# Laser_Teensy_No_AudShield_bckup.net
KiCad netlist of a schematic drawn in EAGLE
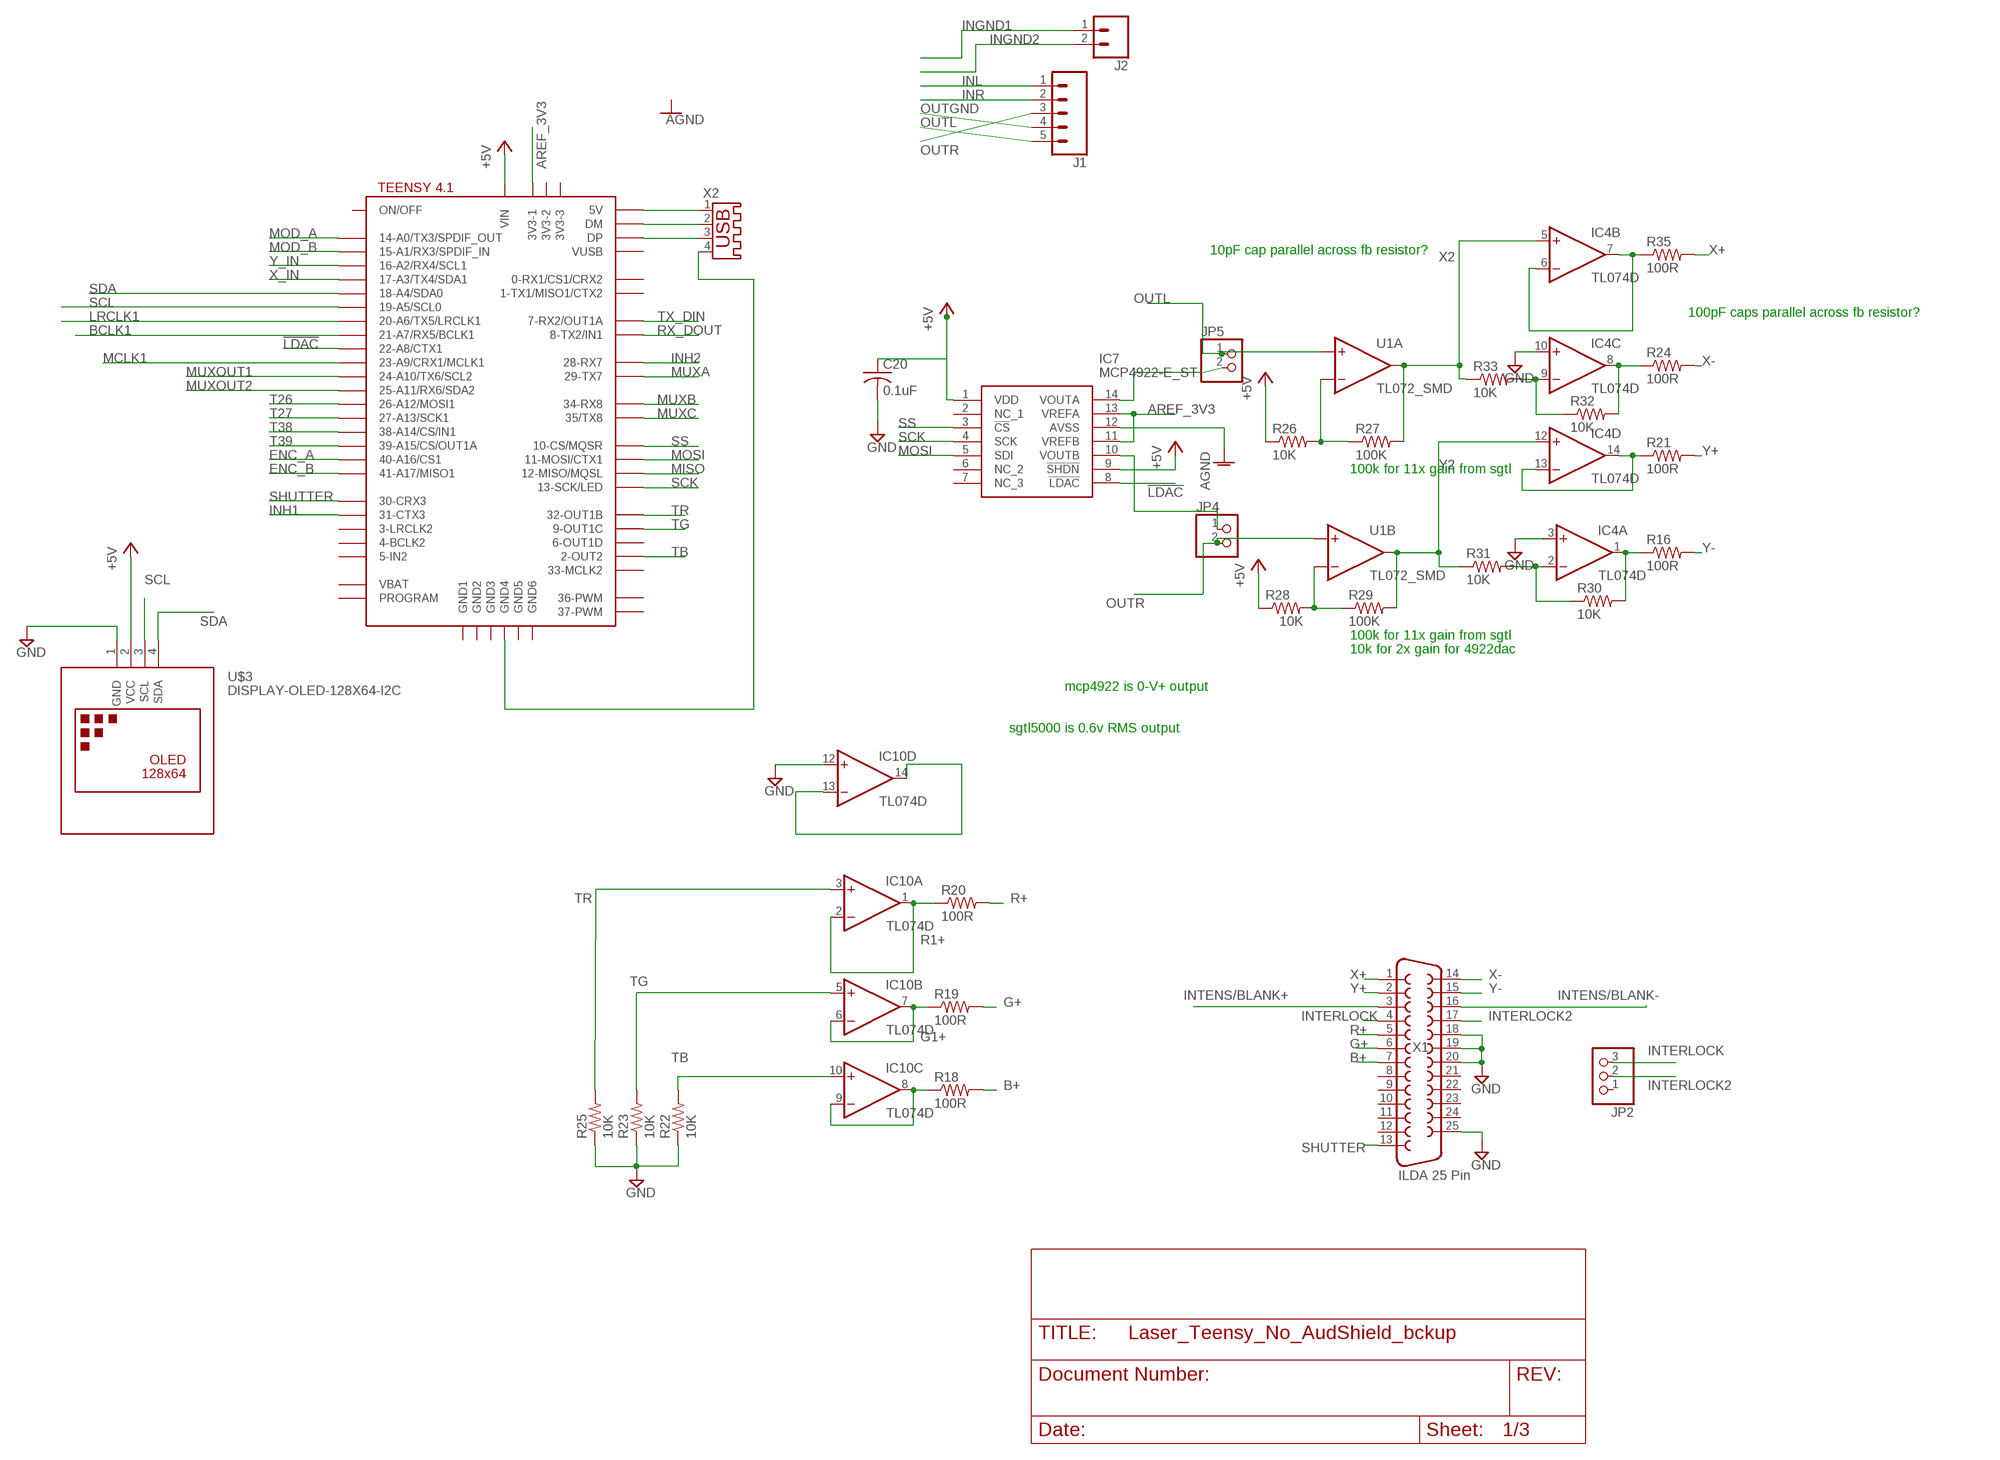
[diagram p0: schematic, sheet 1]
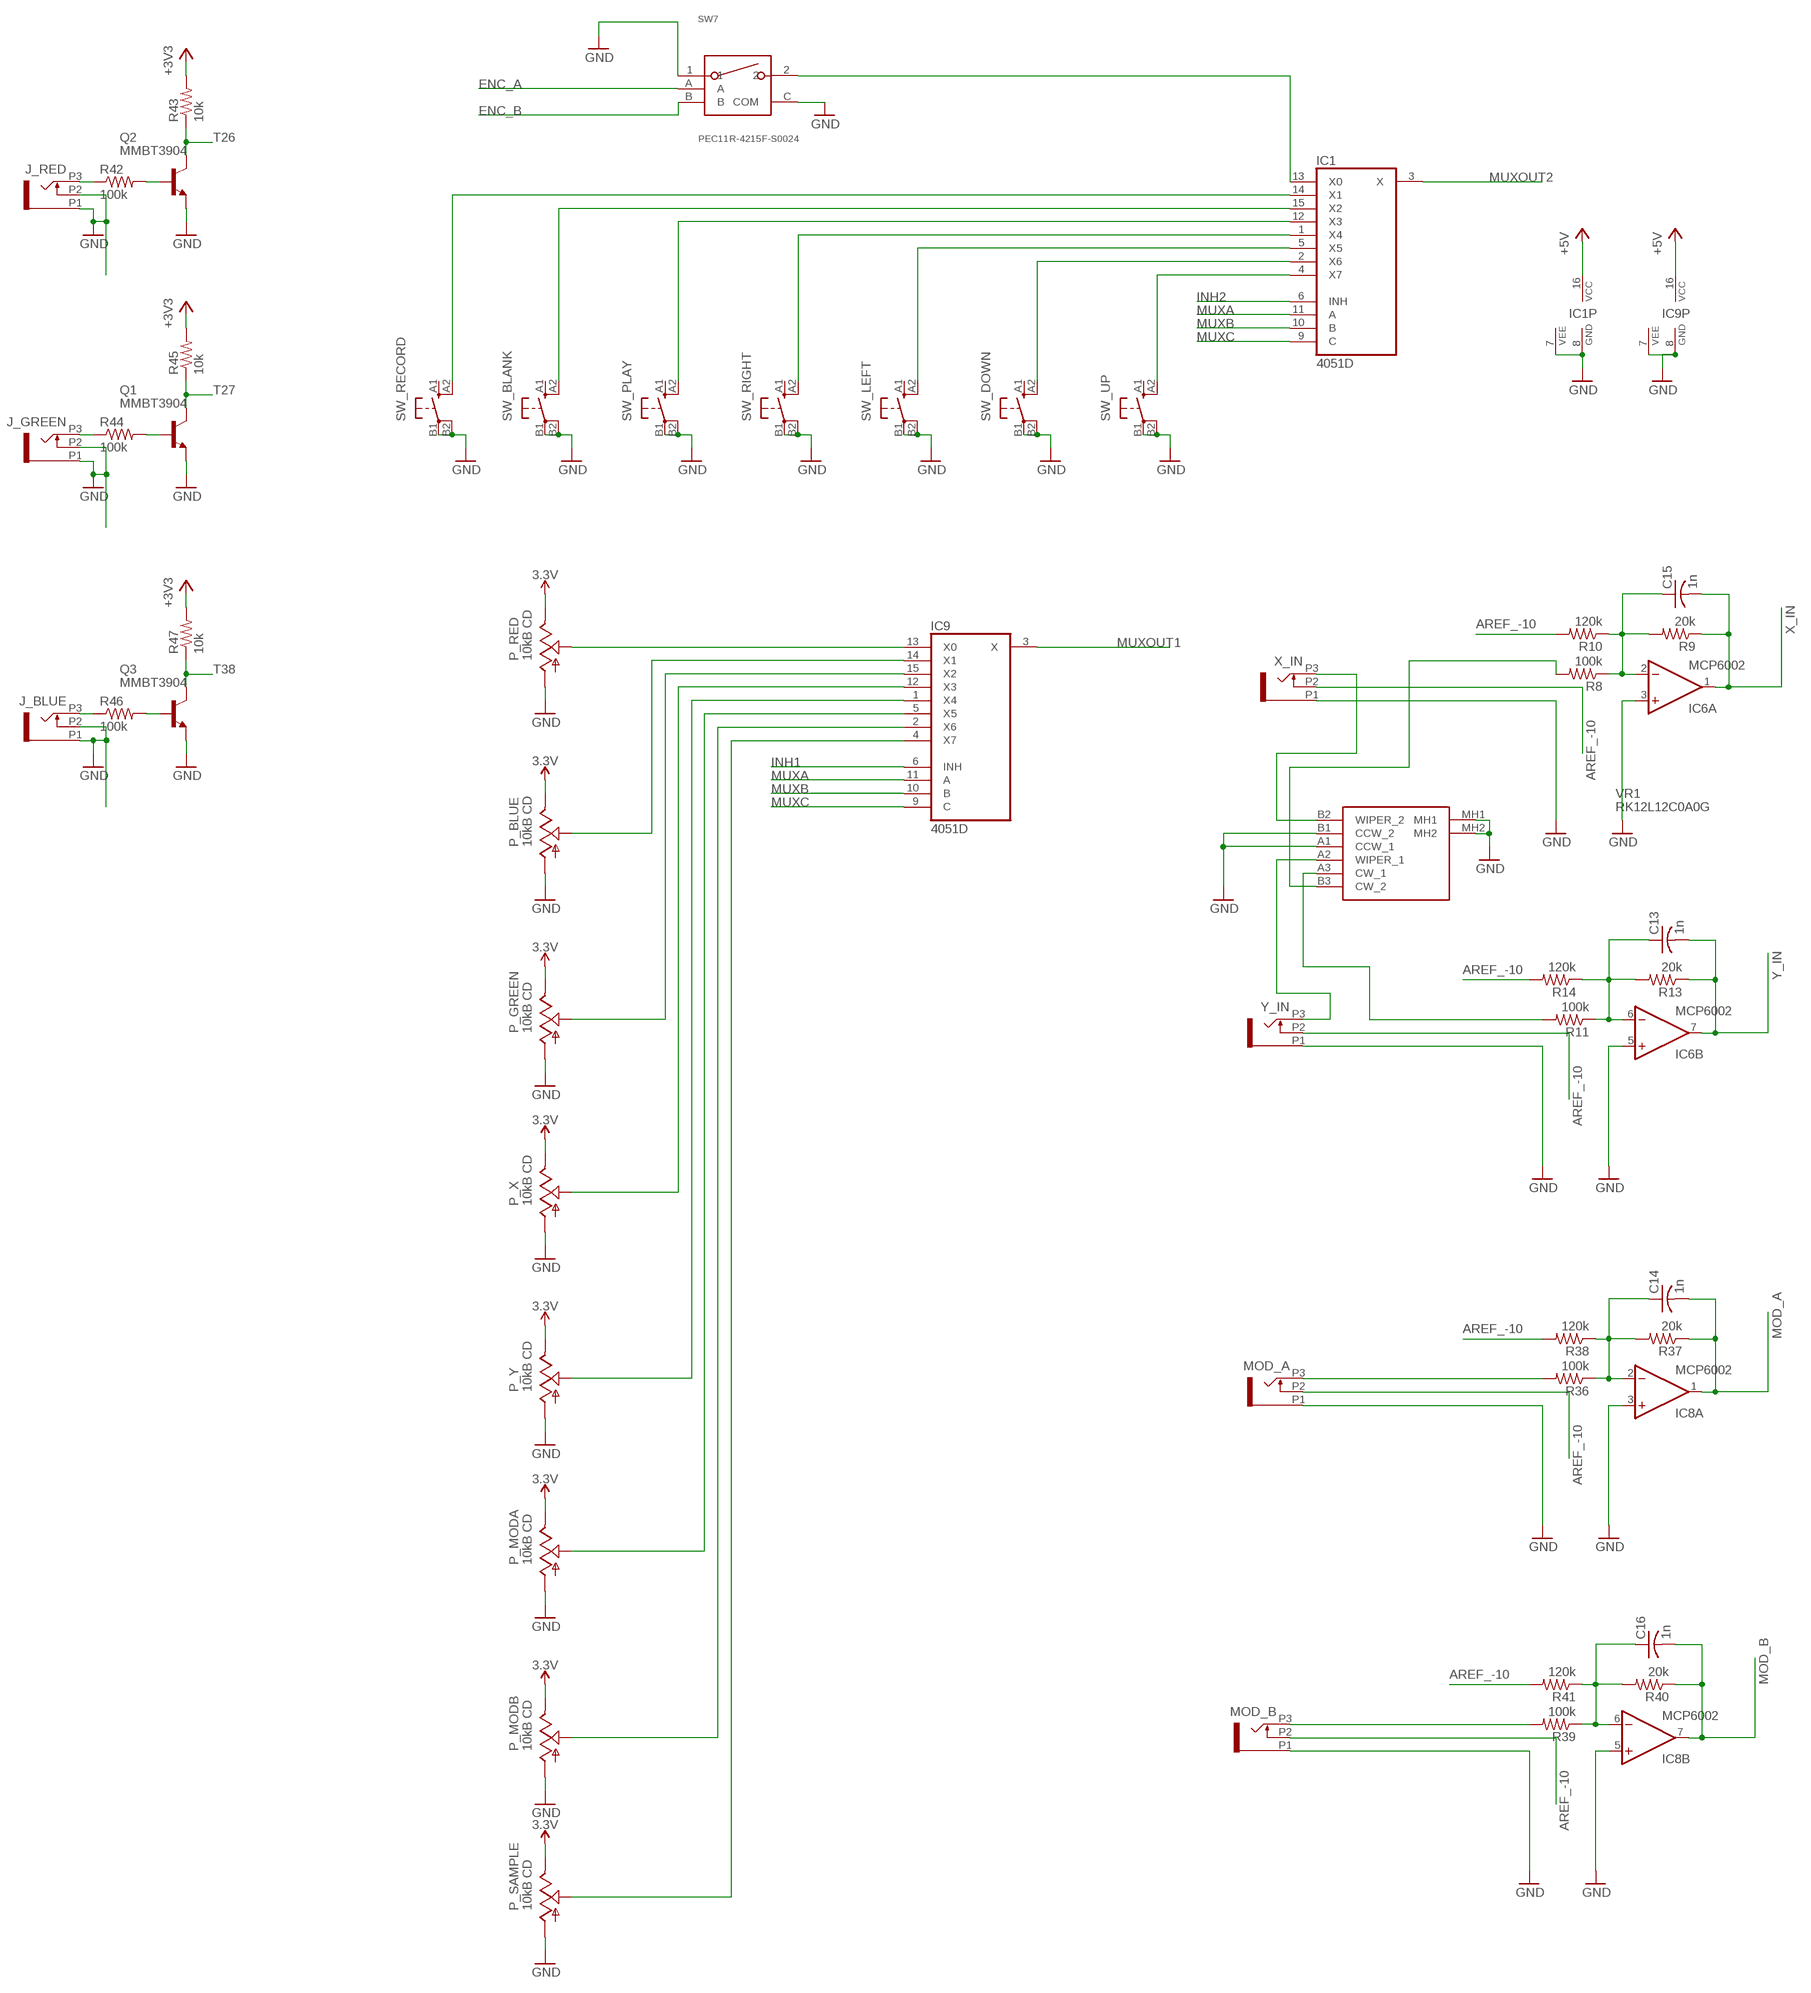
[diagram p1: schematic, sheet 2]
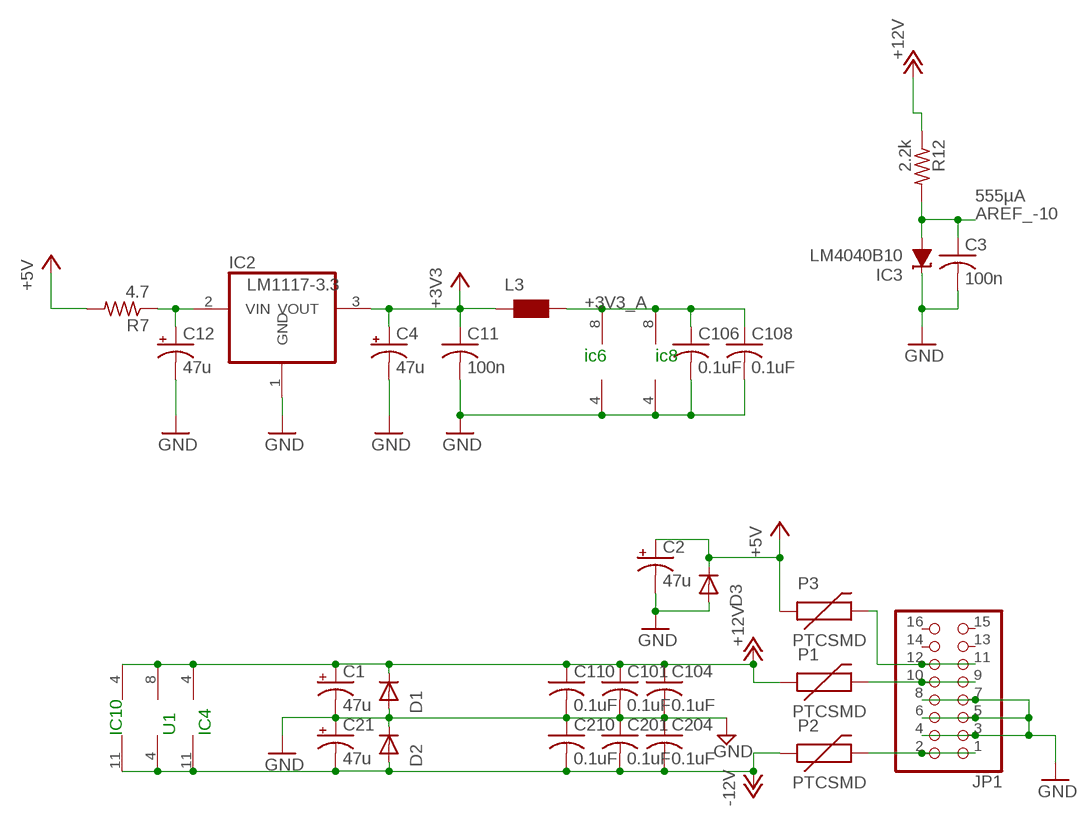
[diagram p2: schematic, sheet 3]

(export (version "E")
  (design (tool "Eeschema 10.0.6"))
  (components
    (comp (ref "C13")
      (value "1n")
      (footprint "eagle-import:C050-025X075")
      (libsource (lib "eagle-import") (part "rcl_334_C-US050-025X075"))
    )
    (comp (ref "C14")
      (value "1n")
      (footprint "eagle-import:C050-025X075")
      (libsource (lib "eagle-import") (part "rcl_334_C-US050-025X075"))
    )
    (comp (ref "C15")
      (value "1n")
      (footprint "eagle-import:C050-025X075")
      (libsource (lib "eagle-import") (part "rcl_334_C-US050-025X075"))
    )
    (comp (ref "C16")
      (value "1n")
      (footprint "eagle-import:C050-025X075")
      (libsource (lib "eagle-import") (part "rcl_334_C-US050-025X075"))
    )
    (comp (ref "IC1")
      (value "4051D")
      (footprint "eagle-import:SO16")
      (libsource (lib "eagle-import") (part "4051D"))
    )
    (comp (ref "IC6")
      (value "MCP6002")
      (footprint "eagle-import:SO08")
      (libsource (lib "eagle-import") (part "TL072D"))
    )
    (comp (ref "IC8")
      (value "MCP6002")
      (footprint "eagle-import:SO08")
      (libsource (lib "eagle-import") (part "TL072D"))
    )
    (comp (ref "IC9")
      (value "4051D")
      (footprint "eagle-import:SO16")
      (libsource (lib "eagle-import") (part "4051D"))
    )
    (comp (ref "J_BLUE")
      (value "PJ301_THONKICONN6")
      (footprint "eagle-import:WQP_PJ_301M6")
      (libsource (lib "eagle-import") (part "PJ301_THONKICONN6"))
    )
    (comp (ref "J_GREEN")
      (value "PJ301_THONKICONN6")
      (footprint "eagle-import:WQP_PJ_301M6")
      (libsource (lib "eagle-import") (part "PJ301_THONKICONN6"))
    )
    (comp (ref "J_RED")
      (value "PJ301_THONKICONN6")
      (footprint "eagle-import:WQP_PJ_301M6")
      (libsource (lib "eagle-import") (part "PJ301_THONKICONN6"))
    )
    (comp (ref "MOD_A")
      (value "PJ301_THONKICONN6")
      (footprint "eagle-import:WQP_PJ_301M6")
      (libsource (lib "eagle-import") (part "og-pj301_variations_PJ301_THONKICONN6"))
    )
    (comp (ref "MOD_B")
      (value "PJ301_THONKICONN6")
      (footprint "eagle-import:WQP_PJ_301M6")
      (libsource (lib "eagle-import") (part "og-pj301_variations_PJ301_THONKICONN6"))
    )
    (comp (ref "P_BLUE")
      (value "10kB CD")
      (footprint "eagle-import:ALPS_POT_VERTICAL_PS")
      (libsource (lib "eagle-import") (part "POT_USVERTICAL_PS"))
    )
    (comp (ref "P_GREEN")
      (value "10kB CD")
      (footprint "eagle-import:ALPS_POT_VERTICAL_PS")
      (libsource (lib "eagle-import") (part "POT_USVERTICAL_PS"))
    )
    (comp (ref "P_MODA")
      (value "10kB CD")
      (footprint "eagle-import:ALPS_POT_VERTICAL_PS")
      (libsource (lib "eagle-import") (part "POT_USVERTICAL_PS"))
    )
    (comp (ref "P_MODB")
      (value "10kB CD")
      (footprint "eagle-import:ALPS_POT_VERTICAL_PS")
      (libsource (lib "eagle-import") (part "POT_USVERTICAL_PS"))
    )
    (comp (ref "P_RED")
      (value "10kB CD")
      (footprint "eagle-import:ALPS_POT_VERTICAL_PS")
      (libsource (lib "eagle-import") (part "POT_USVERTICAL_PS"))
    )
    (comp (ref "P_SAMPLE")
      (value "10kB CD")
      (footprint "eagle-import:ALPS_POT_VERTICAL_PS")
      (libsource (lib "eagle-import") (part "POT_USVERTICAL_PS"))
    )
    (comp (ref "P_X")
      (value "10kB CD")
      (footprint "eagle-import:ALPS_POT_VERTICAL_PS")
      (libsource (lib "eagle-import") (part "POT_USVERTICAL_PS"))
    )
    (comp (ref "P_Y")
      (value "10kB CD")
      (footprint "eagle-import:ALPS_POT_VERTICAL_PS")
      (libsource (lib "eagle-import") (part "POT_USVERTICAL_PS"))
    )
    (comp (ref "Q1")
      (value "MMBT3904")
      (footprint "eagle-import:SOT23-BEC")
      (libsource (lib "eagle-import") (part "-NPN-SOT23-BECMMBT3904LT1"))
    )
    (comp (ref "Q2")
      (value "MMBT3904")
      (footprint "eagle-import:SOT23-BEC")
      (libsource (lib "eagle-import") (part "-NPN-SOT23-BECMMBT3904LT1"))
    )
    (comp (ref "Q3")
      (value "MMBT3904")
      (footprint "eagle-import:SOT23-BEC")
      (libsource (lib "eagle-import") (part "-NPN-SOT23-BECMMBT3904LT1"))
    )
    (comp (ref "R8")
      (value "100k")
      (footprint "eagle-import:0204_5")
      (libsource (lib "eagle-import") (part "rcl_334_R-US_0204/5"))
    )
    (comp (ref "R9")
      (value "20k")
      (footprint "eagle-import:0204_5")
      (libsource (lib "eagle-import") (part "rcl_334_R-US_0204/5"))
    )
    (comp (ref "R10")
      (value "120k")
      (footprint "eagle-import:0204_5")
      (libsource (lib "eagle-import") (part "rcl_334_R-US_0204/5"))
    )
    (comp (ref "R11")
      (value "100k")
      (footprint "eagle-import:0204_5")
      (libsource (lib "eagle-import") (part "rcl_334_R-US_0204/5"))
    )
    (comp (ref "R13")
      (value "20k")
      (footprint "eagle-import:0204_5")
      (libsource (lib "eagle-import") (part "rcl_334_R-US_0204/5"))
    )
    (comp (ref "R14")
      (value "120k")
      (footprint "eagle-import:0204_5")
      (libsource (lib "eagle-import") (part "rcl_334_R-US_0204/5"))
    )
    (comp (ref "R36")
      (value "100k")
      (footprint "eagle-import:0204_5")
      (libsource (lib "eagle-import") (part "rcl_334_R-US_0204/5"))
    )
    (comp (ref "R37")
      (value "20k")
      (footprint "eagle-import:0204_5")
      (libsource (lib "eagle-import") (part "rcl_334_R-US_0204/5"))
    )
    (comp (ref "R38")
      (value "120k")
      (footprint "eagle-import:0204_5")
      (libsource (lib "eagle-import") (part "rcl_334_R-US_0204/5"))
    )
    (comp (ref "R39")
      (value "100k")
      (footprint "eagle-import:0204_5")
      (libsource (lib "eagle-import") (part "rcl_334_R-US_0204/5"))
    )
    (comp (ref "R40")
      (value "20k")
      (footprint "eagle-import:0204_5")
      (libsource (lib "eagle-import") (part "rcl_334_R-US_0204/5"))
    )
    (comp (ref "R41")
      (value "120k")
      (footprint "eagle-import:0204_5")
      (libsource (lib "eagle-import") (part "rcl_334_R-US_0204/5"))
    )
    (comp (ref "R42")
      (value "100k")
      (footprint "eagle-import:0204_5")
      (libsource (lib "eagle-import") (part "rcl_334_R-US_0204/5"))
    )
    (comp (ref "R43")
      (value "10k")
      (footprint "eagle-import:0204_5")
      (libsource (lib "eagle-import") (part "rcl_334_R-US_0204/5"))
    )
    (comp (ref "R44")
      (value "100k")
      (footprint "eagle-import:0204_5")
      (libsource (lib "eagle-import") (part "rcl_334_R-US_0204/5"))
    )
    (comp (ref "R45")
      (value "10k")
      (footprint "eagle-import:0204_5")
      (libsource (lib "eagle-import") (part "rcl_334_R-US_0204/5"))
    )
    (comp (ref "R46")
      (value "100k")
      (footprint "eagle-import:0204_5")
      (libsource (lib "eagle-import") (part "rcl_334_R-US_0204/5"))
    )
    (comp (ref "R47")
      (value "10k")
      (footprint "eagle-import:0204_5")
      (libsource (lib "eagle-import") (part "rcl_334_R-US_0204/5"))
    )
    (comp (ref "SW7")
      (value "PEC11R-4215F-S0024")
      (footprint "eagle-import:PEC11R-4215F-S0024")
      (fields
        (field (name "DIGIKEY_PART_NUMBER") "PEC11R-4215F-S0024-ND")
        (field (name "MANUFACTURER") "Bourns Inc.")
        (field (name "CREATED_BY") "PCBLayout.com")
      )
      (libsource (lib "eagle-import") (part "PEC11R-4215F-S0024"))
    )
    (comp (ref "SW_BLANK")
      (value "D6R")
      (footprint "eagle-import:D6R")
      (libsource (lib "eagle-import") (part "D6R"))
    )
    (comp (ref "SW_DOWN")
      (value "D6R")
      (footprint "eagle-import:D6R")
      (libsource (lib "eagle-import") (part "D6R"))
    )
    (comp (ref "SW_LEFT")
      (value "D6R")
      (footprint "eagle-import:D6R")
      (libsource (lib "eagle-import") (part "D6R"))
    )
    (comp (ref "SW_PLAY")
      (value "D6R")
      (footprint "eagle-import:D6R")
      (libsource (lib "eagle-import") (part "D6R"))
    )
    (comp (ref "SW_RECORD")
      (value "D6R")
      (footprint "eagle-import:D6R")
      (libsource (lib "eagle-import") (part "D6R"))
    )
    (comp (ref "SW_RIGHT")
      (value "D6R")
      (footprint "eagle-import:D6R")
      (libsource (lib "eagle-import") (part "D6R"))
    )
    (comp (ref "SW_UP")
      (value "D6R")
      (footprint "eagle-import:D6R")
      (libsource (lib "eagle-import") (part "D6R"))
    )
    (comp (ref "VR1")
      (value "RK12L12C0A0G")
      (footprint "eagle-import:RK12L12C0A0G")
      (fields (field (name "MOUSER_PART_NUMBER") "688-RK12L12C0A0G"))
      (libsource (lib "eagle-import") (part "RK12L12C0A0G"))
    )
    (comp (ref "X_IN")
      (value "PJ301_THONKICONN6")
      (footprint "eagle-import:WQP_PJ_301M6")
      (libsource (lib "eagle-import") (part "og-pj301_variations_PJ301_THONKICONN6"))
    )
    (comp (ref "Y_IN")
      (value "PJ301_THONKICONN6")
      (footprint "eagle-import:WQP_PJ_301M6")
      (libsource (lib "eagle-import") (part "og-pj301_variations_PJ301_THONKICONN6"))
    )
    (comp (ref "C1")
      (value "47u")
      (footprint "eagle-import:E3,5-8")
      (libsource (lib "eagle-import") (part "CPOL-USE3.5-8"))
    )
    (comp (ref "C2")
      (value "47u")
      (footprint "eagle-import:E3,5-8")
      (libsource (lib "eagle-import") (part "CPOL-USE3.5-8"))
    )
    (comp (ref "C3")
      (value "100n")
      (footprint "eagle-import:C0603")
      (libsource (lib "eagle-import") (part "rcl_C-USC0603"))
    )
    (comp (ref "C4")
      (value "47u")
      (footprint "eagle-import:E3,5-8")
      (libsource (lib "eagle-import") (part "CPOL-USE3.5-8"))
    )
    (comp (ref "C11")
      (value "100n")
      (footprint "eagle-import:C0603")
      (libsource (lib "eagle-import") (part "rcl_C-USC0603"))
    )
    (comp (ref "C12")
      (value "47u")
      (footprint "eagle-import:E3,5-8")
      (libsource (lib "eagle-import") (part "CPOL-USE3.5-8"))
    )
    (comp (ref "C21")
      (value "47u")
      (footprint "eagle-import:E3,5-8")
      (libsource (lib "eagle-import") (part "CPOL-USE3.5-8"))
    )
    (comp (ref "C101")
      (value "0.1uF")
      (footprint "eagle-import:C0603")
      (libsource (lib "eagle-import") (part "C-USC0603"))
    )
    (comp (ref "C104")
      (value "0.1uF")
      (footprint "eagle-import:C0603")
      (libsource (lib "eagle-import") (part "C-USC0603"))
    )
    (comp (ref "C106")
      (value "0.1uF")
      (footprint "eagle-import:C0603")
      (libsource (lib "eagle-import") (part "C-USC0603"))
    )
    (comp (ref "C108")
      (value "0.1uF")
      (footprint "eagle-import:C0603")
      (libsource (lib "eagle-import") (part "C-USC0603"))
    )
    (comp (ref "C110")
      (value "0.1uF")
      (footprint "eagle-import:C0603")
      (libsource (lib "eagle-import") (part "C-USC0603"))
    )
    (comp (ref "C201")
      (value "0.1uF")
      (footprint "eagle-import:C0603")
      (libsource (lib "eagle-import") (part "C-USC0603"))
    )
    (comp (ref "C204")
      (value "0.1uF")
      (footprint "eagle-import:C0603")
      (libsource (lib "eagle-import") (part "C-USC0603"))
    )
    (comp (ref "C210")
      (value "0.1uF")
      (footprint "eagle-import:C0603")
      (libsource (lib "eagle-import") (part "C-USC0603"))
    )
    (comp (ref "D1")
      (value "1N5819HW")
      (footprint "eagle-import:SOD123")
      (libsource (lib "eagle-import") (part "DIODE-SOD123"))
    )
    (comp (ref "D2")
      (value "1N5819HW")
      (footprint "eagle-import:SOD123")
      (libsource (lib "eagle-import") (part "DIODE-SOD123"))
    )
    (comp (ref "D3")
      (value "1N5819HW")
      (footprint "eagle-import:SOD123")
      (libsource (lib "eagle-import") (part "DIODE-SOD123"))
    )
    (comp (ref "IC2")
      (value "LM1117-3.3")
      (footprint "eagle-import:TO252")
      (libsource (lib "eagle-import") (part "REG1117T"))
    )
    (comp (ref "IC3")
      (value "LM4040B10")
      (footprint "eagle-import:DBZ_R-PDSO-G3")
      (libsource (lib "eagle-import") (part "LM4041DBZB12"))
    )
    (comp (ref "IC4")
      (value "TL074D")
      (footprint "eagle-import:SO14")
      (libsource (lib "eagle-import") (part "TL074D"))
    )
    (comp (ref "IC10")
      (value "TL074D")
      (footprint "eagle-import:SO14")
      (libsource (lib "eagle-import") (part "TL074D"))
    )
    (comp (ref "JP1")
      (value "PINHD-2X8")
      (footprint "eagle-import:2X08")
      (libsource (lib "eagle-import") (part "PINHD-2X8"))
    )
    (comp (ref "L3")
      (value "WE-CBF_0603")
      (footprint "eagle-import:0603")
      (libsource (lib "eagle-import") (part "WE-CBF_0603"))
    )
    (comp (ref "P1")
      (value "PTCSMD")
      (footprint "eagle-import:PTC-1206")
      (libsource (lib "eagle-import") (part "PTCSMD"))
    )
    (comp (ref "P2")
      (value "PTCSMD")
      (footprint "eagle-import:PTC-1206")
      (libsource (lib "eagle-import") (part "PTCSMD"))
    )
    (comp (ref "P3")
      (value "PTCSMD")
      (footprint "eagle-import:PTC-1206")
      (libsource (lib "eagle-import") (part "PTCSMD"))
    )
    (comp (ref "R7")
      (value "4.7")
      (footprint "eagle-import:R1206")
      (libsource (lib "eagle-import") (part "R-US_R1206"))
    )
    (comp (ref "R12")
      (value "2.2k")
      (footprint "eagle-import:0204_5")
      (libsource (lib "eagle-import") (part "rcl_334_R-US_0204/5"))
    )
    (comp (ref "U1")
      (value "TL072_SMD")
      (footprint "eagle-import:SO08")
      (libsource (lib "eagle-import") (part "TL072_SMD"))
    )
    (comp (ref "C20")
      (value "0.1uF")
      (footprint "eagle-import:C0603")
      (libsource (lib "eagle-import") (part "C-USC0603"))
    )
    (comp (ref "IC7")
      (value "MCP4922-E_ST")
      (footprint "eagle-import:SOP65P638X110-14N")
      (fields
        (field (name "ARROW_PART_NUMBER") "MCP4922-E/ST")
        (field (name "MOUSER_PART_NUMBER") "579-MCP4922-E/ST")
      )
      (libsource (lib "eagle-import") (part "MCP4922-E_ST"))
    )
    (comp (ref "J1")
      (value "CONN_05")
      (footprint "eagle-import:1X05")
      (libsource (lib "eagle-import") (part "CONN_05"))
    )
    (comp (ref "J2")
      (value "CONN_02")
      (footprint "eagle-import:1X02")
      (libsource (lib "eagle-import") (part "CONN_02"))
    )
    (comp (ref "JP2")
      (value "PINHD-1X3")
      (footprint "eagle-import:1X03")
      (libsource (lib "eagle-import") (part "PINHD-1X3"))
    )
    (comp (ref "JP4")
      (value "PINHD-1X2")
      (footprint "eagle-import:1X02")
      (libsource (lib "eagle-import") (part "PINHD-1X2"))
    )
    (comp (ref "JP5")
      (value "PINHD-1X2")
      (footprint "eagle-import:1X02")
      (libsource (lib "eagle-import") (part "PINHD-1X2"))
    )
    (comp (ref "R16")
      (value "100R")
      (footprint "eagle-import:0204_5")
      (libsource (lib "eagle-import") (part "rcl_334_R-US_0204/5"))
    )
    (comp (ref "R18")
      (value "100R")
      (footprint "eagle-import:0204_5")
      (libsource (lib "eagle-import") (part "rcl_334_R-US_0204/5"))
    )
    (comp (ref "R19")
      (value "100R")
      (footprint "eagle-import:0204_5")
      (libsource (lib "eagle-import") (part "rcl_334_R-US_0204/5"))
    )
    (comp (ref "R20")
      (value "100R")
      (footprint "eagle-import:0204_5")
      (libsource (lib "eagle-import") (part "rcl_334_R-US_0204/5"))
    )
    (comp (ref "R21")
      (value "100R")
      (footprint "eagle-import:0204_5")
      (libsource (lib "eagle-import") (part "rcl_334_R-US_0204/5"))
    )
    (comp (ref "R22")
      (value "10K")
      (footprint "eagle-import:0204_5")
      (libsource (lib "eagle-import") (part "rcl_334_R-US_0204/5"))
    )
    (comp (ref "R23")
      (value "10K")
      (footprint "eagle-import:0204_5")
      (libsource (lib "eagle-import") (part "rcl_334_R-US_0204/5"))
    )
    (comp (ref "R24")
      (value "100R")
      (footprint "eagle-import:0204_5")
      (libsource (lib "eagle-import") (part "rcl_334_R-US_0204/5"))
    )
    (comp (ref "R25")
      (value "10K")
      (footprint "eagle-import:0204_5")
      (libsource (lib "eagle-import") (part "rcl_334_R-US_0204/5"))
    )
    (comp (ref "R26")
      (value "10K")
      (footprint "eagle-import:0204_5")
      (libsource (lib "eagle-import") (part "rcl_334_R-US_0204/5"))
    )
    (comp (ref "R27")
      (value "100K")
      (footprint "eagle-import:0204_5")
      (libsource (lib "eagle-import") (part "rcl_334_R-US_0204/5"))
    )
    (comp (ref "R28")
      (value "10K")
      (footprint "eagle-import:0204_5")
      (libsource (lib "eagle-import") (part "rcl_334_R-US_0204/5"))
    )
    (comp (ref "R29")
      (value "100K")
      (footprint "eagle-import:0204_5")
      (libsource (lib "eagle-import") (part "rcl_334_R-US_0204/5"))
    )
    (comp (ref "R30")
      (value "10K")
      (footprint "eagle-import:0204_5")
      (libsource (lib "eagle-import") (part "rcl_334_R-US_0204/5"))
    )
    (comp (ref "R31")
      (value "10K")
      (footprint "eagle-import:0204_5")
      (libsource (lib "eagle-import") (part "rcl_334_R-US_0204/5"))
    )
    (comp (ref "R32")
      (value "10K")
      (footprint "eagle-import:R0603")
      (libsource (lib "eagle-import") (part "resistor_R-US_R0603"))
    )
    (comp (ref "R33")
      (value "10K")
      (footprint "eagle-import:0204_5")
      (libsource (lib "eagle-import") (part "rcl_334_R-US_0204/5"))
    )
    (comp (ref "R35")
      (value "100R")
      (footprint "eagle-import:0204_5")
      (libsource (lib "eagle-import") (part "rcl_334_R-US_0204/5"))
    )
    (comp (ref "U$2")
      (value "TEENSY41-E")
      (footprint "eagle-import:TENNSY41-E")
      (libsource (lib "eagle-import") (part "TEENSY41-E"))
    )
    (comp (ref "U$3")
      (value "DISPLAY-OLED-128X64-I2C")
      (footprint "eagle-import:DISPLAY-OLED-128X64-I2C")
      (libsource (lib "eagle-import") (part "DISPLAY-OLED-128X64-I2C"))
    )
    (comp (ref "X1")
      (value "ILDA 25 Pin")
      (footprint "eagle-import:F25D")
      (libsource (lib "eagle-import") (part "F25D"))
    )
    (comp (ref "X2")
      (value "USB-A003")
      (footprint "eagle-import:USB-A003")
      (libsource (lib "eagle-import") (part "USB-A003"))
    )
  )
  (nets
    (net (code "1") (name "+3V3") (class "Default")
      (node (ref "C11") (pin "1") (pinfunction "1_1") (pintype "passive"))
      (node (ref "C4") (pin "+") (pinfunction "+_+") (pintype "passive"))
      (node (ref "IC2") (pin "3") (pinfunction "VOUT_3") (pintype "output"))
      (node (ref "L3") (pin "1") (pinfunction "1_1") (pintype "passive"))
      (node (ref "R43") (pin "2") (pinfunction "2_2") (pintype "passive"))
      (node (ref "R45") (pin "2") (pinfunction "2_2") (pintype "passive"))
      (node (ref "R47") (pin "2") (pinfunction "2_2") (pintype "passive"))
    )
    (net (code "2") (name "+3V3_A") (class "Default")
      (node (ref "C106") (pin "1") (pinfunction "1_1") (pintype "passive"))
      (node (ref "C108") (pin "1") (pinfunction "1_1") (pintype "passive"))
      (node (ref "IC6") (pin "8") (pinfunction "V+_8") (pintype "power_in"))
      (node (ref "IC8") (pin "8") (pinfunction "V+_8") (pintype "power_in"))
      (node (ref "L3") (pin "2") (pinfunction "2_2") (pintype "passive"))
    )
    (net (code "3") (name "+5V") (class "Default")
      (node (ref "C2") (pin "+") (pinfunction "+_+") (pintype "passive"))
      (node (ref "C20") (pin "1") (pinfunction "1_1") (pintype "passive"))
      (node (ref "D3") (pin "C") (pinfunction "C_C") (pintype "passive"))
      (node (ref "IC1") (pin "16") (pinfunction "VCC_16") (pintype "power_in"))
      (node (ref "IC7") (pin "1") (pinfunction "VDD_1") (pintype "bidirectional"))
      (node (ref "IC7") (pin "9") (pinfunction "~{SHDN}_9") (pintype "bidirectional"))
      (node (ref "IC9") (pin "16") (pinfunction "VCC_16") (pintype "power_in"))
      (node (ref "P3") (pin "1") (pinfunction "1_1") (pintype "bidirectional"))
      (node (ref "R26") (pin "1") (pinfunction "1_1") (pintype "passive"))
      (node (ref "R28") (pin "1") (pinfunction "1_1") (pintype "passive"))
      (node (ref "R7") (pin "2") (pinfunction "2_2") (pintype "passive"))
      (node (ref "U$2") (pin "VIN") (pinfunction "VIN_VIN") (pintype "bidirectional"))
      (node (ref "U$3") (pin "2") (pinfunction "VCC_2") (pintype "power_in"))
    )
    (net (code "4") (name "+12V") (class "Default")
      (node (ref "C1") (pin "+") (pinfunction "+_+") (pintype "passive"))
      (node (ref "C101") (pin "1") (pinfunction "1_1") (pintype "passive"))
      (node (ref "C104") (pin "1") (pinfunction "1_1") (pintype "passive"))
      (node (ref "C110") (pin "1") (pinfunction "1_1") (pintype "passive"))
      (node (ref "D1") (pin "C") (pinfunction "C_C") (pintype "passive"))
      (node (ref "IC10") (pin "4") (pinfunction "V+_4") (pintype "power_in"))
      (node (ref "IC4") (pin "4") (pinfunction "V+_4") (pintype "power_in"))
      (node (ref "P1") (pin "1") (pinfunction "1_1") (pintype "bidirectional"))
      (node (ref "R12") (pin "1") (pinfunction "1_1") (pintype "passive"))
      (node (ref "U1") (pin "8") (pinfunction "V+_8") (pintype "power_in"))
    )
    (net (code "5") (name "-12V") (class "Default")
      (node (ref "C201") (pin "2") (pinfunction "2_2") (pintype "passive"))
      (node (ref "C204") (pin "2") (pinfunction "2_2") (pintype "passive"))
      (node (ref "C21") (pin "-") (pinfunction "-_-") (pintype "passive"))
      (node (ref "C210") (pin "2") (pinfunction "2_2") (pintype "passive"))
      (node (ref "D2") (pin "A") (pinfunction "A_A") (pintype "passive"))
      (node (ref "IC10") (pin "11") (pinfunction "V-_11") (pintype "power_in"))
      (node (ref "IC4") (pin "11") (pinfunction "V-_11") (pintype "power_in"))
      (node (ref "P2") (pin "1") (pinfunction "1_1") (pintype "bidirectional"))
      (node (ref "U1") (pin "4") (pinfunction "V-_4") (pintype "power_in"))
    )
    (net (code "6") (name "3.3V") (class "Default")
      (node (ref "P_BLUE") (pin "P$1") (pinfunction "E_P$1") (pintype "passive"))
      (node (ref "P_GREEN") (pin "P$1") (pinfunction "E_P$1") (pintype "passive"))
      (node (ref "P_MODA") (pin "P$1") (pinfunction "E_P$1") (pintype "passive"))
      (node (ref "P_MODB") (pin "P$1") (pinfunction "E_P$1") (pintype "passive"))
      (node (ref "P_RED") (pin "P$1") (pinfunction "E_P$1") (pintype "passive"))
      (node (ref "P_SAMPLE") (pin "P$1") (pinfunction "E_P$1") (pintype "passive"))
      (node (ref "P_X") (pin "P$1") (pinfunction "E_P$1") (pintype "passive"))
      (node (ref "P_Y") (pin "P$1") (pinfunction "E_P$1") (pintype "passive"))
    )
    (net (code "7") (name "AGND") (class "Default")
      (node (ref "IC7") (pin "12") (pinfunction "AVSS_12") (pintype "bidirectional"))
    )
    (net (code "8") (name "AREF_-10") (class "Default")
      (node (ref "C3") (pin "1") (pinfunction "1_1") (pintype "passive"))
      (node (ref "IC3") (pin "2") (pinfunction "A_2") (pintype "passive"))
      (node (ref "MOD_A") (pin "P2") (pinfunction "2_P2") (pintype "passive"))
      (node (ref "MOD_B") (pin "P2") (pinfunction "2_P2") (pintype "passive"))
      (node (ref "R10") (pin "2") (pinfunction "2_2") (pintype "passive"))
      (node (ref "R12") (pin "2") (pinfunction "2_2") (pintype "passive"))
      (node (ref "R14") (pin "2") (pinfunction "2_2") (pintype "passive"))
      (node (ref "R38") (pin "2") (pinfunction "2_2") (pintype "passive"))
      (node (ref "R41") (pin "2") (pinfunction "2_2") (pintype "passive"))
      (node (ref "X_IN") (pin "P2") (pinfunction "2_P2") (pintype "passive"))
      (node (ref "Y_IN") (pin "P2") (pinfunction "2_P2") (pintype "passive"))
    )
    (net (code "9") (name "AREF_3V3") (class "Default")
      (node (ref "IC7") (pin "11") (pinfunction "VREFB_11") (pintype "bidirectional"))
      (node (ref "IC7") (pin "13") (pinfunction "VREFA_13") (pintype "bidirectional"))
      (node (ref "U$2") (pin "3V3-1") (pinfunction "3V3-1_3V3-1") (pintype "bidirectional"))
    )
    (net (code "10") (name "B+") (class "Default")
      (node (ref "R18") (pin "2") (pinfunction "2_2") (pintype "passive"))
      (node (ref "X1") (pin "7") (pinfunction "7_7") (pintype "passive"))
    )
    (net (code "11") (name "BCLK1") (class "Default")
      (node (ref "U$2") (pin "21-A7/RX5/BCLK1") (pinfunction "21-A7/RX5/BCLK1_21-A7/RX5/BCLK1") (pintype "bidirectional"))
    )
    (net (code "12") (name "ENC_A") (class "Default")
      (node (ref "SW7") (pin "A") (pinfunction "A_A") (pintype "passive"))
      (node (ref "U$2") (pin "40-A16/CS1") (pinfunction "40-A16/CS1_40-A16/CS1") (pintype "bidirectional"))
    )
    (net (code "13") (name "ENC_B") (class "Default")
      (node (ref "SW7") (pin "B") (pinfunction "B_B") (pintype "passive"))
      (node (ref "U$2") (pin "41-A17/MISO1") (pinfunction "41-A17/MISO1_41-A17/MISO1") (pintype "bidirectional"))
    )
    (net (code "14") (name "G+") (class "Default")
      (node (ref "R19") (pin "2") (pinfunction "2_2") (pintype "passive"))
      (node (ref "X1") (pin "6") (pinfunction "6_6") (pintype "passive"))
    )
    (net (code "15") (name "G1+") (class "Default")
      (node (ref "IC10") (pin "6") (pinfunction "-IN_6") (pintype "input"))
      (node (ref "IC10") (pin "7") (pinfunction "OUT_7") (pintype "output"))
      (node (ref "R19") (pin "1") (pinfunction "1_1") (pintype "passive"))
    )
    (net (code "16") (name "GND") (class "Default")
      (node (ref "C1") (pin "-") (pinfunction "-_-") (pintype "passive"))
      (node (ref "C101") (pin "2") (pinfunction "2_2") (pintype "passive"))
      (node (ref "C104") (pin "2") (pinfunction "2_2") (pintype "passive"))
      (node (ref "C106") (pin "2") (pinfunction "2_2") (pintype "passive"))
      (node (ref "C108") (pin "2") (pinfunction "2_2") (pintype "passive"))
      (node (ref "C11") (pin "2") (pinfunction "2_2") (pintype "passive"))
      (node (ref "C110") (pin "2") (pinfunction "2_2") (pintype "passive"))
      (node (ref "C12") (pin "-") (pinfunction "-_-") (pintype "passive"))
      (node (ref "C2") (pin "-") (pinfunction "-_-") (pintype "passive"))
      (node (ref "C20") (pin "2") (pinfunction "2_2") (pintype "passive"))
      (node (ref "C201") (pin "1") (pinfunction "1_1") (pintype "passive"))
      (node (ref "C204") (pin "1") (pinfunction "1_1") (pintype "passive"))
      (node (ref "C21") (pin "+") (pinfunction "+_+") (pintype "passive"))
      (node (ref "C210") (pin "1") (pinfunction "1_1") (pintype "passive"))
      (node (ref "C3") (pin "2") (pinfunction "2_2") (pintype "passive"))
      (node (ref "C4") (pin "-") (pinfunction "-_-") (pintype "passive"))
      (node (ref "D1") (pin "A") (pinfunction "A_A") (pintype "passive"))
      (node (ref "D2") (pin "C") (pinfunction "C_C") (pintype "passive"))
      (node (ref "D3") (pin "A") (pinfunction "A_A") (pintype "passive"))
      (node (ref "IC1") (pin "7") (pinfunction "VEE_7") (pintype "power_in"))
      (node (ref "IC1") (pin "8") (pinfunction "GND_8") (pintype "power_in"))
      (node (ref "IC10") (pin "12") (pinfunction "+IN_12") (pintype "input"))
      (node (ref "IC2") (pin "1") (pinfunction "GND_1") (pintype "power_in"))
      (node (ref "IC3") (pin "1") (pinfunction "C_1") (pintype "passive"))
      (node (ref "IC4") (pin "10") (pinfunction "+IN_10") (pintype "input"))
      (node (ref "IC4") (pin "3") (pinfunction "+IN_3") (pintype "input"))
      (node (ref "IC6") (pin "3") (pinfunction "+IN_3") (pintype "input"))
      (node (ref "IC6") (pin "4") (pinfunction "V-_4") (pintype "power_in"))
      (node (ref "IC6") (pin "5") (pinfunction "+IN_5") (pintype "input"))
      (node (ref "IC8") (pin "3") (pinfunction "+IN_3") (pintype "input"))
      (node (ref "IC8") (pin "4") (pinfunction "V-_4") (pintype "power_in"))
      (node (ref "IC8") (pin "5") (pinfunction "+IN_5") (pintype "input"))
      (node (ref "IC9") (pin "7") (pinfunction "VEE_7") (pintype "power_in"))
      (node (ref "IC9") (pin "8") (pinfunction "GND_8") (pintype "power_in"))
      (node (ref "JP1") (pin "3") (pinfunction "3_3") (pintype "passive"))
      (node (ref "JP1") (pin "4") (pinfunction "4_4") (pintype "passive"))
      (node (ref "JP1") (pin "5") (pinfunction "5_5") (pintype "passive"))
      (node (ref "JP1") (pin "6") (pinfunction "6_6") (pintype "passive"))
      (node (ref "JP1") (pin "7") (pinfunction "7_7") (pintype "passive"))
      (node (ref "JP1") (pin "8") (pinfunction "8_8") (pintype "passive"))
      (node (ref "J_BLUE") (pin "P1") (pinfunction "1_P1") (pintype "passive"))
      (node (ref "J_BLUE") (pin "P2") (pinfunction "2_P2") (pintype "passive"))
      (node (ref "J_GREEN") (pin "P1") (pinfunction "1_P1") (pintype "passive"))
      (node (ref "J_GREEN") (pin "P2") (pinfunction "2_P2") (pintype "passive"))
      (node (ref "J_RED") (pin "P1") (pinfunction "1_P1") (pintype "passive"))
      (node (ref "J_RED") (pin "P2") (pinfunction "2_P2") (pintype "passive"))
      (node (ref "MOD_A") (pin "P1") (pinfunction "1_P1") (pintype "passive"))
      (node (ref "MOD_B") (pin "P1") (pinfunction "1_P1") (pintype "passive"))
      (node (ref "P_BLUE") (pin "P$3") (pinfunction "A_P$3") (pintype "passive"))
      (node (ref "P_GREEN") (pin "P$3") (pinfunction "A_P$3") (pintype "passive"))
      (node (ref "P_MODA") (pin "P$3") (pinfunction "A_P$3") (pintype "passive"))
      (node (ref "P_MODB") (pin "P$3") (pinfunction "A_P$3") (pintype "passive"))
      (node (ref "P_RED") (pin "P$3") (pinfunction "A_P$3") (pintype "passive"))
      (node (ref "P_SAMPLE") (pin "P$3") (pinfunction "A_P$3") (pintype "passive"))
      (node (ref "P_X") (pin "P$3") (pinfunction "A_P$3") (pintype "passive"))
      (node (ref "P_Y") (pin "P$3") (pinfunction "A_P$3") (pintype "passive"))
      (node (ref "Q1") (pin "E") (pinfunction "E_E") (pintype "passive"))
      (node (ref "Q2") (pin "E") (pinfunction "E_E") (pintype "passive"))
      (node (ref "Q3") (pin "E") (pinfunction "E_E") (pintype "passive"))
      (node (ref "R22") (pin "1") (pinfunction "1_1") (pintype "passive"))
      (node (ref "R23") (pin "1") (pinfunction "1_1") (pintype "passive"))
      (node (ref "R25") (pin "1") (pinfunction "1_1") (pintype "passive"))
      (node (ref "SW7") (pin "1") (pinfunction "1_1") (pintype "passive"))
      (node (ref "SW7") (pin "C") (pinfunction "COM_C") (pintype "passive"))
      (node (ref "SW_BLANK") (pin "B1") (pinfunction "P_B1") (pintype "passive"))
      (node (ref "SW_BLANK") (pin "B2") (pinfunction "P1_B2") (pintype "passive"))
      (node (ref "SW_DOWN") (pin "B1") (pinfunction "P_B1") (pintype "passive"))
      (node (ref "SW_DOWN") (pin "B2") (pinfunction "P1_B2") (pintype "passive"))
      (node (ref "SW_LEFT") (pin "B1") (pinfunction "P_B1") (pintype "passive"))
      (node (ref "SW_LEFT") (pin "B2") (pinfunction "P1_B2") (pintype "passive"))
      (node (ref "SW_PLAY") (pin "B1") (pinfunction "P_B1") (pintype "passive"))
      (node (ref "SW_PLAY") (pin "B2") (pinfunction "P1_B2") (pintype "passive"))
      (node (ref "SW_RECORD") (pin "B1") (pinfunction "P_B1") (pintype "passive"))
      (node (ref "SW_RECORD") (pin "B2") (pinfunction "P1_B2") (pintype "passive"))
      (node (ref "SW_RIGHT") (pin "B1") (pinfunction "P_B1") (pintype "passive"))
      (node (ref "SW_RIGHT") (pin "B2") (pinfunction "P1_B2") (pintype "passive"))
      (node (ref "SW_UP") (pin "B1") (pinfunction "P_B1") (pintype "passive"))
      (node (ref "SW_UP") (pin "B2") (pinfunction "P1_B2") (pintype "passive"))
      (node (ref "U$3") (pin "1") (pinfunction "GND_1") (pintype "power_in"))
      (node (ref "VR1") (pin "A1") (pinfunction "CCW_1_A1") (pintype "bidirectional"))
      (node (ref "VR1") (pin "B1") (pinfunction "CCW_2_B1") (pintype "bidirectional"))
      (node (ref "VR1") (pin "MH1") (pinfunction "MH1_MH1") (pintype "bidirectional"))
      (node (ref "VR1") (pin "MH2") (pinfunction "MH2_MH2") (pintype "bidirectional"))
      (node (ref "X1") (pin "18") (pinfunction "18_18") (pintype "passive"))
      (node (ref "X1") (pin "19") (pinfunction "19_19") (pintype "passive"))
      (node (ref "X1") (pin "20") (pinfunction "20_20") (pintype "passive"))
      (node (ref "X1") (pin "25") (pinfunction "25_25") (pintype "passive"))
      (node (ref "X_IN") (pin "P1") (pinfunction "1_P1") (pintype "passive"))
      (node (ref "Y_IN") (pin "P1") (pinfunction "1_P1") (pintype "passive"))
    )
    (net (code "17") (name "INGND1") (class "Default")
      (node (ref "J2") (pin "1") (pinfunction "1_1") (pintype "passive"))
    )
    (net (code "18") (name "INGND2") (class "Default")
      (node (ref "J2") (pin "2") (pinfunction "2_2") (pintype "passive"))
    )
    (net (code "19") (name "INH1") (class "Default")
      (node (ref "IC9") (pin "6") (pinfunction "INH_6") (pintype "input"))
      (node (ref "U$2") (pin "31-CTX3") (pinfunction "31-CTX3_31-CTX3") (pintype "bidirectional"))
    )
    (net (code "20") (name "INH2") (class "Default")
      (node (ref "IC1") (pin "6") (pinfunction "INH_6") (pintype "input"))
      (node (ref "U$2") (pin "28-RX7") (pinfunction "28-RX7_28-RX7") (pintype "bidirectional"))
    )
    (net (code "21") (name "INL") (class "Default")
      (node (ref "J1") (pin "1") (pinfunction "1_1") (pintype "passive"))
    )
    (net (code "22") (name "INR") (class "Default")
      (node (ref "J1") (pin "2") (pinfunction "2_2") (pintype "passive"))
    )
    (net (code "23") (name "INTENS{slash}BLANK+") (class "Default")
      (node (ref "X1") (pin "3") (pinfunction "3_3") (pintype "passive"))
    )
    (net (code "24") (name "INTENS{slash}BLANK-") (class "Default")
      (node (ref "X1") (pin "16") (pinfunction "16_16") (pintype "passive"))
    )
    (net (code "25") (name "INTERLOCK") (class "Default")
      (node (ref "JP2") (pin "3") (pinfunction "3_3") (pintype "passive"))
      (node (ref "X1") (pin "4") (pinfunction "4_4") (pintype "passive"))
    )
    (net (code "26") (name "INTERLOCK2") (class "Default")
      (node (ref "JP2") (pin "2") (pinfunction "2_2") (pintype "passive"))
      (node (ref "X1") (pin "17") (pinfunction "17_17") (pintype "passive"))
    )
    (net (code "27") (name "LRCLK1") (class "Default")
      (node (ref "U$2") (pin "20-A6/TX5/LRCLK1") (pinfunction "20-A6/TX5/LRCLK1_20-A6/TX5/LRCLK1") (pintype "bidirectional"))
    )
    (net (code "28") (name "MCLK1") (class "Default")
      (node (ref "U$2") (pin "23-A9/CRX1/MCLK1") (pinfunction "23-A9/CRX1/MCLK1_23-A9/CRX1/MCLK1") (pintype "bidirectional"))
    )
    (net (code "29") (name "MISO") (class "Default")
      (node (ref "U$2") (pin "12-MISO/MQSL") (pinfunction "12-MISO/MQSL_12-MISO/MQSL") (pintype "bidirectional"))
    )
    (net (code "30") (name "MOD_A") (class "Default")
      (node (ref "C14") (pin "2") (pinfunction "2_2") (pintype "passive"))
      (node (ref "IC8") (pin "1") (pinfunction "OUT_1") (pintype "output"))
      (node (ref "R37") (pin "1") (pinfunction "1_1") (pintype "passive"))
      (node (ref "U$2") (pin "14-A0/TX3/SPDIF_OUT") (pinfunction "14-A0/TX3/SPDIF_OUT_14-A0/TX3/SPDIF_OUT") (pintype "bidirectional"))
    )
    (net (code "31") (name "MOD_B") (class "Default")
      (node (ref "C16") (pin "2") (pinfunction "2_2") (pintype "passive"))
      (node (ref "IC8") (pin "7") (pinfunction "OUT_7") (pintype "output"))
      (node (ref "R40") (pin "1") (pinfunction "1_1") (pintype "passive"))
      (node (ref "U$2") (pin "15-A1/RX3/SPDIF_IN") (pinfunction "15-A1/RX3/SPDIF_IN_15-A1/RX3/SPDIF_IN") (pintype "bidirectional"))
    )
    (net (code "32") (name "MOSI") (class "Default")
      (node (ref "IC7") (pin "5") (pinfunction "SDI_5") (pintype "bidirectional"))
      (node (ref "U$2") (pin "11-MOSI/CTX1") (pinfunction "11-MOSI/CTX1_11-MOSI/CTX1") (pintype "bidirectional"))
    )
    (net (code "33") (name "MUXA") (class "Default")
      (node (ref "IC1") (pin "11") (pinfunction "A_11") (pintype "input"))
      (node (ref "IC9") (pin "11") (pinfunction "A_11") (pintype "input"))
      (node (ref "U$2") (pin "29-TX7") (pinfunction "29-TX7_29-TX7") (pintype "bidirectional"))
    )
    (net (code "34") (name "MUXB") (class "Default")
      (node (ref "IC1") (pin "10") (pinfunction "B_10") (pintype "input"))
      (node (ref "IC9") (pin "10") (pinfunction "B_10") (pintype "input"))
      (node (ref "U$2") (pin "34-RX8") (pinfunction "34-RX8_34-RX8") (pintype "bidirectional"))
    )
    (net (code "35") (name "MUXC") (class "Default")
      (node (ref "IC1") (pin "9") (pinfunction "C_9") (pintype "input"))
      (node (ref "IC9") (pin "9") (pinfunction "C_9") (pintype "input"))
      (node (ref "U$2") (pin "35-TX8") (pinfunction "35/TX8_35-TX8") (pintype "bidirectional"))
    )
    (net (code "36") (name "MUXOUT1") (class "Default")
      (node (ref "IC9") (pin "3") (pinfunction "X_3") (pintype "bidirectional"))
      (node (ref "U$2") (pin "24-A10/TX6/SCL2") (pinfunction "24-A10/TX6/SCL2_24-A10/TX6/SCL2") (pintype "bidirectional"))
    )
    (net (code "37") (name "MUXOUT2") (class "Default")
      (node (ref "IC1") (pin "3") (pinfunction "X_3") (pintype "bidirectional"))
      (node (ref "U$2") (pin "25-A11/RX6/SDA2") (pinfunction "25-A11/RX6/SDA2_25-A11/RX6/SDA2") (pintype "bidirectional"))
    )
    (net (code "38") (name "Net-(IC1A-X0)") (class "Default")
      (node (ref "IC1") (pin "13") (pinfunction "X0_13") (pintype "bidirectional"))
      (node (ref "SW7") (pin "2") (pinfunction "2_2") (pintype "passive"))
    )
    (net (code "39") (name "Net-(IC1A-X1)") (class "Default")
      (node (ref "IC1") (pin "14") (pinfunction "X1_14") (pintype "bidirectional"))
      (node (ref "SW_RECORD") (pin "A2") (pinfunction "S1_A2") (pintype "passive"))
    )
    (net (code "40") (name "Net-(IC1A-X2)") (class "Default")
      (node (ref "IC1") (pin "15") (pinfunction "X2_15") (pintype "bidirectional"))
      (node (ref "SW_BLANK") (pin "A2") (pinfunction "S1_A2") (pintype "passive"))
    )
    (net (code "41") (name "Net-(IC1A-X3)") (class "Default")
      (node (ref "IC1") (pin "12") (pinfunction "X3_12") (pintype "bidirectional"))
      (node (ref "SW_PLAY") (pin "A2") (pinfunction "S1_A2") (pintype "passive"))
    )
    (net (code "42") (name "Net-(IC1A-X4)") (class "Default")
      (node (ref "IC1") (pin "1") (pinfunction "X4_1") (pintype "bidirectional"))
      (node (ref "SW_RIGHT") (pin "A2") (pinfunction "S1_A2") (pintype "passive"))
    )
    (net (code "43") (name "Net-(IC1A-X5)") (class "Default")
      (node (ref "IC1") (pin "5") (pinfunction "X5_5") (pintype "bidirectional"))
      (node (ref "SW_LEFT") (pin "A2") (pinfunction "S1_A2") (pintype "passive"))
    )
    (net (code "44") (name "Net-(IC1A-X6)") (class "Default")
      (node (ref "IC1") (pin "2") (pinfunction "X6_2") (pintype "bidirectional"))
      (node (ref "SW_DOWN") (pin "A2") (pinfunction "S1_A2") (pintype "passive"))
    )
    (net (code "45") (name "Net-(IC1A-X7)") (class "Default")
      (node (ref "IC1") (pin "4") (pinfunction "X7_4") (pintype "bidirectional"))
      (node (ref "SW_UP") (pin "A2") (pinfunction "S1_A2") (pintype "passive"))
    )
    (net (code "46") (name "Net-(IC2-VIN)") (class "Default")
      (node (ref "C12") (pin "+") (pinfunction "+_+") (pintype "passive"))
      (node (ref "IC2") (pin "2") (pinfunction "VIN_2") (pintype "input"))
      (node (ref "R7") (pin "1") (pinfunction "1_1") (pintype "passive"))
    )
    (net (code "47") (name "Net-(IC4A--IN)") (class "Default")
      (node (ref "IC4") (pin "2") (pinfunction "-IN_2") (pintype "input"))
      (node (ref "R30") (pin "1") (pinfunction "1_1") (pintype "passive"))
      (node (ref "R31") (pin "2") (pinfunction "2_2") (pintype "passive"))
    )
    (net (code "48") (name "Net-(IC4A-OUT)") (class "Default")
      (node (ref "IC4") (pin "1") (pinfunction "OUT_1") (pintype "output"))
      (node (ref "R16") (pin "1") (pinfunction "1_1") (pintype "passive"))
      (node (ref "R30") (pin "2") (pinfunction "2_2") (pintype "passive"))
    )
    (net (code "49") (name "Net-(IC4B--IN)") (class "Default")
      (node (ref "IC4") (pin "6") (pinfunction "-IN_6") (pintype "input"))
      (node (ref "IC4") (pin "7") (pinfunction "OUT_7") (pintype "output"))
      (node (ref "R35") (pin "1") (pinfunction "1_1") (pintype "passive"))
    )
    (net (code "50") (name "Net-(IC4C--IN)") (class "Default")
      (node (ref "IC4") (pin "9") (pinfunction "-IN_9") (pintype "input"))
      (node (ref "R32") (pin "1") (pinfunction "1_1") (pintype "passive"))
      (node (ref "R33") (pin "2") (pinfunction "2_2") (pintype "passive"))
    )
    (net (code "51") (name "Net-(IC4C-OUT)") (class "Default")
      (node (ref "IC4") (pin "8") (pinfunction "OUT_8") (pintype "output"))
      (node (ref "R24") (pin "1") (pinfunction "1_1") (pintype "passive"))
      (node (ref "R32") (pin "2") (pinfunction "2_2") (pintype "passive"))
    )
    (net (code "52") (name "Net-(IC4D--IN)") (class "Default")
      (node (ref "IC4") (pin "13") (pinfunction "-IN_13") (pintype "input"))
      (node (ref "IC4") (pin "14") (pinfunction "OUT_14") (pintype "output"))
      (node (ref "R21") (pin "1") (pinfunction "1_1") (pintype "passive"))
    )
    (net (code "53") (name "Net-(IC6A--IN)") (class "Default")
      (node (ref "C15") (pin "1") (pinfunction "1_1") (pintype "passive"))
      (node (ref "IC6") (pin "2") (pinfunction "-IN_2") (pintype "input"))
      (node (ref "R10") (pin "1") (pinfunction "1_1") (pintype "passive"))
      (node (ref "R8") (pin "1") (pinfunction "1_1") (pintype "passive"))
      (node (ref "R9") (pin "2") (pinfunction "2_2") (pintype "passive"))
    )
    (net (code "54") (name "Net-(IC6B--IN)") (class "Default")
      (node (ref "C13") (pin "1") (pinfunction "1_1") (pintype "passive"))
      (node (ref "IC6") (pin "6") (pinfunction "-IN_6") (pintype "input"))
      (node (ref "R11") (pin "1") (pinfunction "1_1") (pintype "passive"))
      (node (ref "R13") (pin "2") (pinfunction "2_2") (pintype "passive"))
      (node (ref "R14") (pin "1") (pinfunction "1_1") (pintype "passive"))
    )
    (net (code "55") (name "Net-(IC7-VOUTA)") (class "Default")
      (node (ref "IC7") (pin "14") (pinfunction "VOUTA_14") (pintype "bidirectional"))
      (node (ref "JP5") (pin "2") (pinfunction "2_2") (pintype "passive"))
    )
    (net (code "56") (name "Net-(IC7-VOUTB)") (class "Default")
      (node (ref "IC7") (pin "10") (pinfunction "VOUTB_10") (pintype "bidirectional"))
      (node (ref "JP4") (pin "1") (pinfunction "1_1") (pintype "passive"))
    )
    (net (code "57") (name "Net-(IC8A--IN)") (class "Default")
      (node (ref "C14") (pin "1") (pinfunction "1_1") (pintype "passive"))
      (node (ref "IC8") (pin "2") (pinfunction "-IN_2") (pintype "input"))
      (node (ref "R36") (pin "1") (pinfunction "1_1") (pintype "passive"))
      (node (ref "R37") (pin "2") (pinfunction "2_2") (pintype "passive"))
      (node (ref "R38") (pin "1") (pinfunction "1_1") (pintype "passive"))
    )
    (net (code "58") (name "Net-(IC8B--IN)") (class "Default")
      (node (ref "C16") (pin "1") (pinfunction "1_1") (pintype "passive"))
      (node (ref "IC8") (pin "6") (pinfunction "-IN_6") (pintype "input"))
      (node (ref "R39") (pin "1") (pinfunction "1_1") (pintype "passive"))
      (node (ref "R40") (pin "2") (pinfunction "2_2") (pintype "passive"))
      (node (ref "R41") (pin "1") (pinfunction "1_1") (pintype "passive"))
    )
    (net (code "59") (name "Net-(IC9A-X0)") (class "Default")
      (node (ref "IC9") (pin "13") (pinfunction "X0_13") (pintype "bidirectional"))
      (node (ref "P_RED") (pin "P$2") (pinfunction "S_P$2") (pintype "passive"))
    )
    (net (code "60") (name "Net-(IC9A-X1)") (class "Default")
      (node (ref "IC9") (pin "14") (pinfunction "X1_14") (pintype "bidirectional"))
      (node (ref "P_BLUE") (pin "P$2") (pinfunction "S_P$2") (pintype "passive"))
    )
    (net (code "61") (name "Net-(IC9A-X2)") (class "Default")
      (node (ref "IC9") (pin "15") (pinfunction "X2_15") (pintype "bidirectional"))
      (node (ref "P_GREEN") (pin "P$2") (pinfunction "S_P$2") (pintype "passive"))
    )
    (net (code "62") (name "Net-(IC9A-X3)") (class "Default")
      (node (ref "IC9") (pin "12") (pinfunction "X3_12") (pintype "bidirectional"))
      (node (ref "P_X") (pin "P$2") (pinfunction "S_P$2") (pintype "passive"))
    )
    (net (code "63") (name "Net-(IC9A-X4)") (class "Default")
      (node (ref "IC9") (pin "1") (pinfunction "X4_1") (pintype "bidirectional"))
      (node (ref "P_Y") (pin "P$2") (pinfunction "S_P$2") (pintype "passive"))
    )
    (net (code "64") (name "Net-(IC9A-X5)") (class "Default")
      (node (ref "IC9") (pin "5") (pinfunction "X5_5") (pintype "bidirectional"))
      (node (ref "P_MODA") (pin "P$2") (pinfunction "S_P$2") (pintype "passive"))
    )
    (net (code "65") (name "Net-(IC9A-X6)") (class "Default")
      (node (ref "IC9") (pin "2") (pinfunction "X6_2") (pintype "bidirectional"))
      (node (ref "P_MODB") (pin "P$2") (pinfunction "S_P$2") (pintype "passive"))
    )
    (net (code "66") (name "Net-(IC9A-X7)") (class "Default")
      (node (ref "IC9") (pin "4") (pinfunction "X7_4") (pintype "bidirectional"))
      (node (ref "P_SAMPLE") (pin "P$2") (pinfunction "S_P$2") (pintype "passive"))
    )
    (net (code "67") (name "Net-(IC10C--IN)") (class "Default")
      (node (ref "IC10") (pin "8") (pinfunction "OUT_8") (pintype "output"))
      (node (ref "IC10") (pin "9") (pinfunction "-IN_9") (pintype "input"))
      (node (ref "R18") (pin "1") (pinfunction "1_1") (pintype "passive"))
    )
    (net (code "68") (name "Net-(IC10D--IN)") (class "Default")
      (node (ref "IC10") (pin "13") (pinfunction "-IN_13") (pintype "input"))
      (node (ref "IC10") (pin "14") (pinfunction "OUT_14") (pintype "output"))
    )
    (net (code "69") (name "Net-(JP1-Pad1)") (class "Default")
      (node (ref "JP1") (pin "1") (pinfunction "1_1") (pintype "passive"))
      (node (ref "JP1") (pin "2") (pinfunction "2_2") (pintype "passive"))
      (node (ref "P2") (pin "2") (pinfunction "2_2") (pintype "bidirectional"))
    )
    (net (code "70") (name "Net-(JP1-Pad10)") (class "Default")
      (node (ref "JP1") (pin "10") (pinfunction "10_10") (pintype "passive"))
      (node (ref "JP1") (pin "9") (pinfunction "9_9") (pintype "passive"))
      (node (ref "P1") (pin "2") (pinfunction "2_2") (pintype "bidirectional"))
    )
    (net (code "71") (name "Net-(JP1-Pad11)") (class "Default")
      (node (ref "JP1") (pin "11") (pinfunction "11_11") (pintype "passive"))
      (node (ref "JP1") (pin "12") (pinfunction "12_12") (pintype "passive"))
      (node (ref "P3") (pin "2") (pinfunction "2_2") (pintype "bidirectional"))
    )
    (net (code "72") (name "Net-(J_BLUE-3)") (class "Default")
      (node (ref "J_BLUE") (pin "P3") (pinfunction "3_P3") (pintype "passive"))
      (node (ref "R46") (pin "1") (pinfunction "1_1") (pintype "passive"))
    )
    (net (code "73") (name "Net-(J_GREEN-3)") (class "Default")
      (node (ref "J_GREEN") (pin "P3") (pinfunction "3_P3") (pintype "passive"))
      (node (ref "R44") (pin "1") (pinfunction "1_1") (pintype "passive"))
    )
    (net (code "74") (name "Net-(J_RED-3)") (class "Default")
      (node (ref "J_RED") (pin "P3") (pinfunction "3_P3") (pintype "passive"))
      (node (ref "R42") (pin "1") (pinfunction "1_1") (pintype "passive"))
    )
    (net (code "75") (name "Net-(MOD_A-3)") (class "Default")
      (node (ref "MOD_A") (pin "P3") (pinfunction "3_P3") (pintype "passive"))
      (node (ref "R36") (pin "2") (pinfunction "2_2") (pintype "passive"))
    )
    (net (code "76") (name "Net-(MOD_B-3)") (class "Default")
      (node (ref "MOD_B") (pin "P3") (pinfunction "3_P3") (pintype "passive"))
      (node (ref "R39") (pin "2") (pinfunction "2_2") (pintype "passive"))
    )
    (net (code "77") (name "Net-(Q1-PadB)") (class "Default")
      (node (ref "Q1") (pin "B") (pinfunction "B_B") (pintype "passive"))
      (node (ref "R44") (pin "2") (pinfunction "2_2") (pintype "passive"))
    )
    (net (code "78") (name "Net-(Q2-PadB)") (class "Default")
      (node (ref "Q2") (pin "B") (pinfunction "B_B") (pintype "passive"))
      (node (ref "R42") (pin "2") (pinfunction "2_2") (pintype "passive"))
    )
    (net (code "79") (name "Net-(Q3-PadB)") (class "Default")
      (node (ref "Q3") (pin "B") (pinfunction "B_B") (pintype "passive"))
      (node (ref "R46") (pin "2") (pinfunction "2_2") (pintype "passive"))
    )
    (net (code "80") (name "Net-(U$2-5V)") (class "Default")
      (node (ref "U$2") (pin "+5V") (pinfunction "5V_+5V") (pintype "bidirectional"))
      (node (ref "X2") (pin "1") (pinfunction "1_1") (pintype "passive"))
    )
    (net (code "81") (name "Net-(U$2-PadDM)") (class "Default")
      (node (ref "U$2") (pin "DM") (pinfunction "DM_DM") (pintype "bidirectional"))
      (node (ref "X2") (pin "2") (pinfunction "2_2") (pintype "passive"))
    )
    (net (code "82") (name "Net-(U$2-PadDP)") (class "Default")
      (node (ref "U$2") (pin "DP") (pinfunction "DP_DP") (pintype "bidirectional"))
      (node (ref "X2") (pin "3") (pinfunction "3_3") (pintype "passive"))
    )
    (net (code "83") (name "Net-(U$2-PadGND4)") (class "Default")
      (node (ref "U$2") (pin "GND4") (pinfunction "GND4_GND4") (pintype "bidirectional"))
      (node (ref "X2") (pin "4") (pinfunction "4_4") (pintype "passive"))
    )
    (net (code "84") (name "Net-(U1A--IN)") (class "Default")
      (node (ref "R26") (pin "2") (pinfunction "2_2") (pintype "passive"))
      (node (ref "R27") (pin "1") (pinfunction "1_1") (pintype "passive"))
      (node (ref "U1") (pin "2") (pinfunction "-IN_2") (pintype "input"))
    )
    (net (code "85") (name "Net-(U1B--IN)") (class "Default")
      (node (ref "R28") (pin "2") (pinfunction "2_2") (pintype "passive"))
      (node (ref "R29") (pin "1") (pinfunction "1_1") (pintype "passive"))
      (node (ref "U1") (pin "6") (pinfunction "-IN_6") (pintype "input"))
    )
    (net (code "86") (name "Net-(VR1-CW_1)") (class "Default")
      (node (ref "R11") (pin "2") (pinfunction "2_2") (pintype "passive"))
      (node (ref "VR1") (pin "A3") (pinfunction "CW_1_A3") (pintype "bidirectional"))
    )
    (net (code "87") (name "Net-(VR1-CW_2)") (class "Default")
      (node (ref "R8") (pin "2") (pinfunction "2_2") (pintype "passive"))
      (node (ref "VR1") (pin "B3") (pinfunction "CW_2_B3") (pintype "bidirectional"))
    )
    (net (code "88") (name "Net-(VR1-WIPER_1)") (class "Default")
      (node (ref "VR1") (pin "A2") (pinfunction "WIPER_1_A2") (pintype "bidirectional"))
      (node (ref "Y_IN") (pin "P3") (pinfunction "3_P3") (pintype "passive"))
    )
    (net (code "89") (name "Net-(VR1-WIPER_2)") (class "Default")
      (node (ref "VR1") (pin "B2") (pinfunction "WIPER_2_B2") (pintype "bidirectional"))
      (node (ref "X_IN") (pin "P3") (pinfunction "3_P3") (pintype "passive"))
    )
    (net (code "90") (name "OUTGND") (class "Default")
      (node (ref "J1") (pin "4") (pinfunction "4_4") (pintype "passive"))
    )
    (net (code "91") (name "OUTL") (class "Default")
      (node (ref "J1") (pin "5") (pinfunction "5_5") (pintype "passive"))
      (node (ref "JP5") (pin "1") (pinfunction "1_1") (pintype "passive"))
      (node (ref "U1") (pin "3") (pinfunction "+IN_3") (pintype "input"))
    )
    (net (code "92") (name "OUTR") (class "Default")
      (node (ref "J1") (pin "3") (pinfunction "3_3") (pintype "passive"))
      (node (ref "JP4") (pin "2") (pinfunction "2_2") (pintype "passive"))
      (node (ref "U1") (pin "5") (pinfunction "+IN_5") (pintype "input"))
    )
    (net (code "93") (name "R+") (class "Default")
      (node (ref "R20") (pin "2") (pinfunction "2_2") (pintype "passive"))
      (node (ref "X1") (pin "5") (pinfunction "5_5") (pintype "passive"))
    )
    (net (code "94") (name "R1+") (class "Default")
      (node (ref "IC10") (pin "1") (pinfunction "OUT_1") (pintype "output"))
      (node (ref "IC10") (pin "2") (pinfunction "-IN_2") (pintype "input"))
      (node (ref "R20") (pin "1") (pinfunction "1_1") (pintype "passive"))
    )
    (net (code "95") (name "RX_DOUT") (class "Default")
      (node (ref "U$2") (pin "8-TX2/IN1") (pinfunction "8-TX2/IN1_8-TX2/IN1") (pintype "bidirectional"))
    )
    (net (code "96") (name "SCK") (class "Default")
      (node (ref "IC7") (pin "4") (pinfunction "SCK_4") (pintype "bidirectional"))
      (node (ref "U$2") (pin "13-SCK/LED") (pinfunction "13-SCK/LED_13-SCK/LED") (pintype "bidirectional"))
    )
    (net (code "97") (name "SCL") (class "Default")
      (node (ref "U$2") (pin "19-A5/SCL0") (pinfunction "19-A5/SCL0_19-A5/SCL0") (pintype "bidirectional"))
      (node (ref "U$3") (pin "3") (pinfunction "SCL_3") (pintype "bidirectional"))
    )
    (net (code "98") (name "SDA") (class "Default")
      (node (ref "U$2") (pin "18-A4/SDA0") (pinfunction "18-A4/SDA0_18-A4/SDA0") (pintype "bidirectional"))
      (node (ref "U$3") (pin "4") (pinfunction "SDA_4") (pintype "bidirectional"))
    )
    (net (code "99") (name "SHUTTER") (class "Default")
      (node (ref "U$2") (pin "30-CRX3") (pinfunction "30-CRX3_30-CRX3") (pintype "bidirectional"))
      (node (ref "X1") (pin "13") (pinfunction "13_13") (pintype "passive"))
    )
    (net (code "100") (name "SS") (class "Default")
      (node (ref "IC7") (pin "3") (pinfunction "~{CS}_3") (pintype "bidirectional"))
      (node (ref "U$2") (pin "10-CS\\MQSR") (pinfunction "10-CS/MQSR_10-CS\\MQSR") (pintype "bidirectional"))
    )
    (net (code "101") (name "T26") (class "Default")
      (node (ref "Q2") (pin "C") (pinfunction "C_C") (pintype "passive"))
      (node (ref "R43") (pin "1") (pinfunction "1_1") (pintype "passive"))
      (node (ref "U$2") (pin "26-A12/MOSI1") (pinfunction "26-A12/MOSI1_26-A12/MOSI1") (pintype "bidirectional"))
    )
    (net (code "102") (name "T27") (class "Default")
      (node (ref "Q1") (pin "C") (pinfunction "C_C") (pintype "passive"))
      (node (ref "R45") (pin "1") (pinfunction "1_1") (pintype "passive"))
      (node (ref "U$2") (pin "27-A13/SCK1") (pinfunction "27-A13/SCK1_27-A13/SCK1") (pintype "bidirectional"))
    )
    (net (code "103") (name "T38") (class "Default")
      (node (ref "Q3") (pin "C") (pinfunction "C_C") (pintype "passive"))
      (node (ref "R47") (pin "1") (pinfunction "1_1") (pintype "passive"))
      (node (ref "U$2") (pin "38-A14/CS/IN1") (pinfunction "38-A14/CS/IN1_38-A14/CS/IN1") (pintype "bidirectional"))
    )
    (net (code "104") (name "T39") (class "Default")
      (node (ref "U$2") (pin "39-A15/CS/OUT1A") (pinfunction "39-A15/CS/OUT1A_39-A15/CS/OUT1A") (pintype "bidirectional"))
    )
    (net (code "105") (name "TB") (class "Default")
      (node (ref "IC10") (pin "10") (pinfunction "+IN_10") (pintype "input"))
      (node (ref "R22") (pin "2") (pinfunction "2_2") (pintype "passive"))
      (node (ref "U$2") (pin "2-OUT2") (pinfunction "2-OUT2_2-OUT2") (pintype "bidirectional"))
    )
    (net (code "106") (name "TG") (class "Default")
      (node (ref "IC10") (pin "5") (pinfunction "+IN_5") (pintype "input"))
      (node (ref "R23") (pin "2") (pinfunction "2_2") (pintype "passive"))
      (node (ref "U$2") (pin "9-OUT1C") (pinfunction "9-OUT1C_9-OUT1C") (pintype "bidirectional"))
    )
    (net (code "107") (name "TR") (class "Default")
      (node (ref "IC10") (pin "3") (pinfunction "+IN_3") (pintype "input"))
      (node (ref "R25") (pin "2") (pinfunction "2_2") (pintype "passive"))
      (node (ref "U$2") (pin "32-OUT1B") (pinfunction "32-OUT1B_32-OUT1B") (pintype "bidirectional"))
    )
    (net (code "108") (name "TX_DIN") (class "Default")
      (node (ref "U$2") (pin "7-RX2/OUT1A") (pinfunction "7-RX2/OUT1A_7-RX2/OUT1A") (pintype "bidirectional"))
    )
    (net (code "109") (name "X+") (class "Default")
      (node (ref "R35") (pin "2") (pinfunction "2_2") (pintype "passive"))
      (node (ref "X1") (pin "1") (pinfunction "1_1") (pintype "passive"))
    )
    (net (code "110") (name "X-") (class "Default")
      (node (ref "R24") (pin "2") (pinfunction "2_2") (pintype "passive"))
      (node (ref "X1") (pin "14") (pinfunction "14_14") (pintype "passive"))
    )
    (net (code "111") (name "X2") (class "Default")
      (node (ref "IC4") (pin "5") (pinfunction "+IN_5") (pintype "input"))
      (node (ref "R27") (pin "2") (pinfunction "2_2") (pintype "passive"))
      (node (ref "R33") (pin "1") (pinfunction "1_1") (pintype "passive"))
      (node (ref "U1") (pin "1") (pinfunction "OUT_1") (pintype "output"))
    )
    (net (code "112") (name "X_IN") (class "Default")
      (node (ref "C15") (pin "2") (pinfunction "2_2") (pintype "passive"))
      (node (ref "IC6") (pin "1") (pinfunction "OUT_1") (pintype "output"))
      (node (ref "R9") (pin "1") (pinfunction "1_1") (pintype "passive"))
      (node (ref "U$2") (pin "17-A3/TX4/SDA1") (pinfunction "17-A3/TX4/SDA1_17-A3/TX4/SDA1") (pintype "bidirectional"))
    )
    (net (code "113") (name "Y+") (class "Default")
      (node (ref "R21") (pin "2") (pinfunction "2_2") (pintype "passive"))
      (node (ref "X1") (pin "2") (pinfunction "2_2") (pintype "passive"))
    )
    (net (code "114") (name "Y-") (class "Default")
      (node (ref "R16") (pin "2") (pinfunction "2_2") (pintype "passive"))
      (node (ref "X1") (pin "15") (pinfunction "15_15") (pintype "passive"))
    )
    (net (code "115") (name "Y2") (class "Default")
      (node (ref "IC4") (pin "12") (pinfunction "+IN_12") (pintype "input"))
      (node (ref "R29") (pin "2") (pinfunction "2_2") (pintype "passive"))
      (node (ref "R31") (pin "1") (pinfunction "1_1") (pintype "passive"))
      (node (ref "U1") (pin "7") (pinfunction "OUT_7") (pintype "output"))
    )
    (net (code "116") (name "Y_IN") (class "Default")
      (node (ref "C13") (pin "2") (pinfunction "2_2") (pintype "passive"))
      (node (ref "IC6") (pin "7") (pinfunction "OUT_7") (pintype "output"))
      (node (ref "R13") (pin "1") (pinfunction "1_1") (pintype "passive"))
      (node (ref "U$2") (pin "16-A2/RX4/SCL1") (pinfunction "16-A2/RX4/SCL1_16-A2/RX4/SCL1") (pintype "bidirectional"))
    )
    (net (code "117") (name "unconnected-(IC7-NC_1-Pad2)") (class "Default")
      (node (ref "IC7") (pin "2") (pinfunction "NC_1_2") (pintype "bidirectional"))
    )
    (net (code "118") (name "unconnected-(IC7-NC_2-Pad6)") (class "Default")
      (node (ref "IC7") (pin "6") (pinfunction "NC_2_6") (pintype "bidirectional"))
    )
    (net (code "119") (name "unconnected-(IC7-NC_3-Pad7)") (class "Default")
      (node (ref "IC7") (pin "7") (pinfunction "NC_3_7") (pintype "bidirectional"))
    )
    (net (code "120") (name "unconnected-(JP1-Pad13)") (class "Default")
      (node (ref "JP1") (pin "13") (pinfunction "13_13") (pintype "passive"))
    )
    (net (code "121") (name "unconnected-(JP1-Pad14)") (class "Default")
      (node (ref "JP1") (pin "14") (pinfunction "14_14") (pintype "passive"))
    )
    (net (code "122") (name "unconnected-(JP1-Pad15)") (class "Default")
      (node (ref "JP1") (pin "15") (pinfunction "15_15") (pintype "passive"))
    )
    (net (code "123") (name "unconnected-(JP1-Pad16)") (class "Default")
      (node (ref "JP1") (pin "16") (pinfunction "16_16") (pintype "passive"))
    )
    (net (code "124") (name "unconnected-(JP2-Pad1)") (class "Default")
      (node (ref "JP2") (pin "1") (pinfunction "1_1") (pintype "passive"))
    )
    (net (code "125") (name "unconnected-(SW_BLANK-S-PadA1)") (class "Default")
      (node (ref "SW_BLANK") (pin "A1") (pinfunction "S_A1") (pintype "passive"))
    )
    (net (code "126") (name "unconnected-(SW_DOWN-S-PadA1)") (class "Default")
      (node (ref "SW_DOWN") (pin "A1") (pinfunction "S_A1") (pintype "passive"))
    )
    (net (code "127") (name "unconnected-(SW_LEFT-S-PadA1)") (class "Default")
      (node (ref "SW_LEFT") (pin "A1") (pinfunction "S_A1") (pintype "passive"))
    )
    (net (code "128") (name "unconnected-(SW_PLAY-S-PadA1)") (class "Default")
      (node (ref "SW_PLAY") (pin "A1") (pinfunction "S_A1") (pintype "passive"))
    )
    (net (code "129") (name "unconnected-(SW_RECORD-S-PadA1)") (class "Default")
      (node (ref "SW_RECORD") (pin "A1") (pinfunction "S_A1") (pintype "passive"))
    )
    (net (code "130") (name "unconnected-(SW_RIGHT-S-PadA1)") (class "Default")
      (node (ref "SW_RIGHT") (pin "A1") (pinfunction "S_A1") (pintype "passive"))
    )
    (net (code "131") (name "unconnected-(SW_UP-S-PadA1)") (class "Default")
      (node (ref "SW_UP") (pin "A1") (pinfunction "S_A1") (pintype "passive"))
    )
    (net (code "132") (name "unconnected-(U$2-Pad0-RX1{slash}CS1{slash}CRX2)") (class "Default")
      (node (ref "U$2") (pin "0-RX1/CS1/CRX2") (pinfunction "0-RX1/CS1/CRX2_0-RX1/CS1/CRX2") (pintype "bidirectional"))
    )
    (net (code "133") (name "unconnected-(U$2-Pad1-TX1{slash}MISO1{slash}CTX2)") (class "Default")
      (node (ref "U$2") (pin "1-TX1/MISO1/CTX2") (pinfunction "1-TX1/MISO1/CTX2_1-TX1/MISO1/CTX2") (pintype "bidirectional"))
    )
    (net (code "134") (name "unconnected-(U$2-Pad3-LRCLK2)") (class "Default")
      (node (ref "U$2") (pin "3-LRCLK2") (pinfunction "3-LRCLK2_3-LRCLK2") (pintype "bidirectional"))
    )
    (net (code "135") (name "unconnected-(U$2-Pad3V3-2)") (class "Default")
      (node (ref "U$2") (pin "3V3-2") (pinfunction "3V3-2_3V3-2") (pintype "bidirectional"))
    )
    (net (code "136") (name "unconnected-(U$2-Pad3V3-3)") (class "Default")
      (node (ref "U$2") (pin "3V3-3") (pinfunction "3V3-3_3V3-3") (pintype "bidirectional"))
    )
    (net (code "137") (name "unconnected-(U$2-Pad4-BCLK2)") (class "Default")
      (node (ref "U$2") (pin "4-BCLK2") (pinfunction "4-BCLK2_4-BCLK2") (pintype "bidirectional"))
    )
    (net (code "138") (name "unconnected-(U$2-Pad5-IN2)") (class "Default")
      (node (ref "U$2") (pin "5-IN2") (pinfunction "5-IN2_5-IN2") (pintype "bidirectional"))
    )
    (net (code "139") (name "unconnected-(U$2-Pad6-OUT1D)") (class "Default")
      (node (ref "U$2") (pin "6-OUT1D") (pinfunction "6-OUT1D_6-OUT1D") (pintype "bidirectional"))
    )
    (net (code "140") (name "unconnected-(U$2-Pad33-MCLK2)") (class "Default")
      (node (ref "U$2") (pin "33-MCLK2") (pinfunction "33-MCLK2_33-MCLK2") (pintype "bidirectional"))
    )
    (net (code "141") (name "unconnected-(U$2-Pad36-PWM)") (class "Default")
      (node (ref "U$2") (pin "36-PWM") (pinfunction "36-PWM_36-PWM") (pintype "bidirectional"))
    )
    (net (code "142") (name "unconnected-(U$2-Pad37-PWM)") (class "Default")
      (node (ref "U$2") (pin "37-PWM") (pinfunction "37-PWM_37-PWM") (pintype "bidirectional"))
    )
    (net (code "143") (name "unconnected-(U$2-PadGND1)") (class "Default")
      (node (ref "U$2") (pin "GND1") (pinfunction "GND1_GND1") (pintype "bidirectional"))
    )
    (net (code "144") (name "unconnected-(U$2-PadGND2)") (class "Default")
      (node (ref "U$2") (pin "GND2") (pinfunction "GND2_GND2") (pintype "bidirectional"))
    )
    (net (code "145") (name "unconnected-(U$2-PadGND3)") (class "Default")
      (node (ref "U$2") (pin "GND3") (pinfunction "GND3_GND3") (pintype "bidirectional"))
    )
    (net (code "146") (name "unconnected-(U$2-PadGND5)") (class "Default")
      (node (ref "U$2") (pin "GND5") (pinfunction "GND5_GND5") (pintype "bidirectional"))
    )
    (net (code "147") (name "unconnected-(U$2-PadGND6)") (class "Default")
      (node (ref "U$2") (pin "GND6") (pinfunction "GND6_GND6") (pintype "bidirectional"))
    )
    (net (code "148") (name "unconnected-(U$2-PadON{slash}OFF)") (class "Default")
      (node (ref "U$2") (pin "ON/OFF") (pinfunction "ON/OFF_ON/OFF") (pintype "bidirectional"))
    )
    (net (code "149") (name "unconnected-(U$2-PadPROGRAM)") (class "Default")
      (node (ref "U$2") (pin "PROGRAM") (pinfunction "PROGRAM_PROGRAM") (pintype "bidirectional"))
    )
    (net (code "150") (name "unconnected-(U$2-PadVBAT)") (class "Default")
      (node (ref "U$2") (pin "VBAT") (pinfunction "VBAT_VBAT") (pintype "bidirectional"))
    )
    (net (code "151") (name "unconnected-(U$2-PadVUSB)") (class "Default")
      (node (ref "U$2") (pin "VUSB") (pinfunction "VUSB_VUSB") (pintype "bidirectional"))
    )
    (net (code "152") (name "unconnected-(X1-Pad8)") (class "Default")
      (node (ref "X1") (pin "8") (pinfunction "8_8") (pintype "passive"))
    )
    (net (code "153") (name "unconnected-(X1-Pad9)") (class "Default")
      (node (ref "X1") (pin "9") (pinfunction "9_9") (pintype "passive"))
    )
    (net (code "154") (name "unconnected-(X1-Pad10)") (class "Default")
      (node (ref "X1") (pin "10") (pinfunction "10_10") (pintype "passive"))
    )
    (net (code "155") (name "unconnected-(X1-Pad11)") (class "Default")
      (node (ref "X1") (pin "11") (pinfunction "11_11") (pintype "passive"))
    )
    (net (code "156") (name "unconnected-(X1-Pad12)") (class "Default")
      (node (ref "X1") (pin "12") (pinfunction "12_12") (pintype "passive"))
    )
    (net (code "157") (name "unconnected-(X1-Pad21)") (class "Default")
      (node (ref "X1") (pin "21") (pinfunction "21_21") (pintype "passive"))
    )
    (net (code "158") (name "unconnected-(X1-Pad22)") (class "Default")
      (node (ref "X1") (pin "22") (pinfunction "22_22") (pintype "passive"))
    )
    (net (code "159") (name "unconnected-(X1-Pad23)") (class "Default")
      (node (ref "X1") (pin "23") (pinfunction "23_23") (pintype "passive"))
    )
    (net (code "160") (name "unconnected-(X1-Pad24)") (class "Default")
      (node (ref "X1") (pin "24") (pinfunction "24_24") (pintype "passive"))
    )
    (net (code "161") (name "~{LDAC}") (class "Default")
      (node (ref "IC7") (pin "8") (pinfunction "~{LDAC}_8") (pintype "bidirectional"))
      (node (ref "U$2") (pin "22-A8/CTX1") (pinfunction "22-A8/CTX1_22-A8/CTX1") (pintype "bidirectional"))
    )
  )
)
